# ProPrj__Windows_Hello_DIAL_HUB__2024-08-.net
KiCad netlist of a schematic drawn in EasyEDA Pro
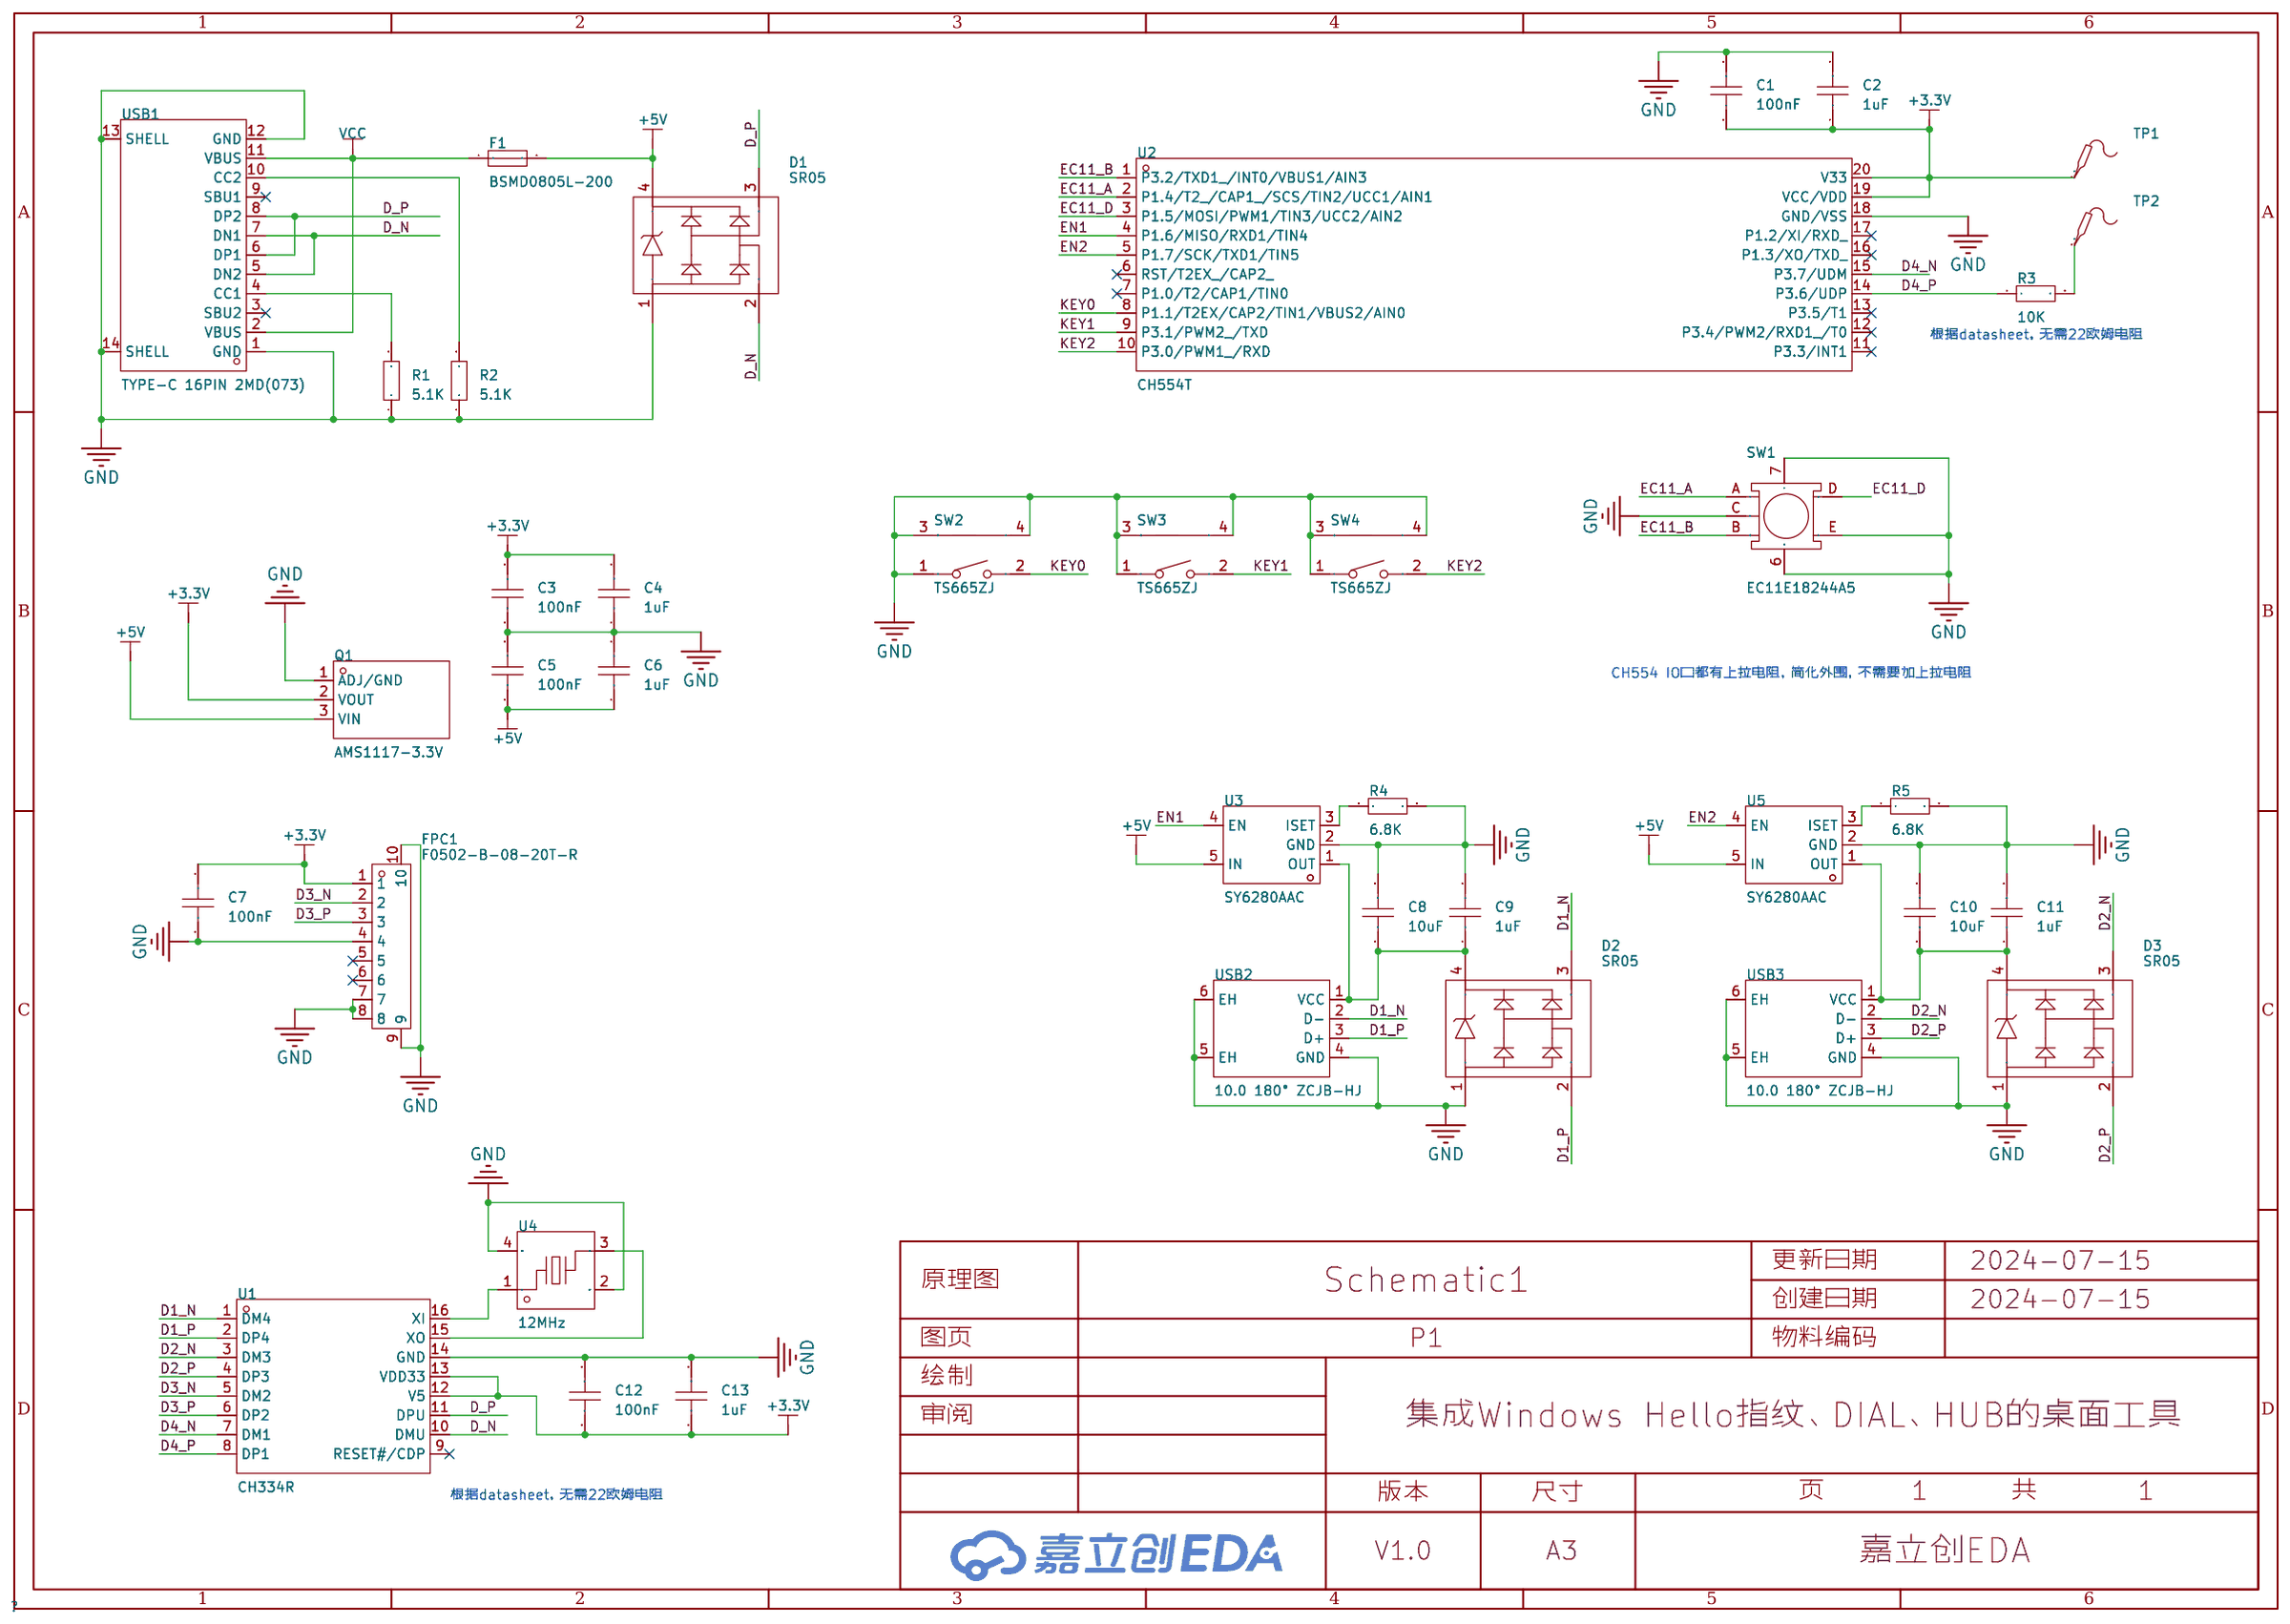
[diagram p0: schematic sheet]

(export (version "E")
  (design (tool "Eeschema 10.0.6"))
  (components
    (comp (ref "C1")
      (value "100nF")
      (footprint "easyedapro:C0603")
      (libsource (lib "easyedapro") (part "CapAcitance"))
    )
    (comp (ref "C2")
      (value "1uF")
      (footprint "easyedapro:C0603")
      (libsource (lib "easyedapro") (part "CapAcitance"))
    )
    (comp (ref "C3")
      (value "100nF")
      (footprint "easyedapro:C0603")
      (libsource (lib "easyedapro") (part "CapAcitance"))
    )
    (comp (ref "C4")
      (value "1uF")
      (footprint "easyedapro:C0603")
      (libsource (lib "easyedapro") (part "CapAcitance"))
    )
    (comp (ref "C5")
      (value "100nF")
      (footprint "easyedapro:C0603")
      (libsource (lib "easyedapro") (part "CapAcitance"))
    )
    (comp (ref "C6")
      (value "1uF")
      (footprint "easyedapro:C0603")
      (libsource (lib "easyedapro") (part "CapAcitance"))
    )
    (comp (ref "C7")
      (value "100nF")
      (footprint "easyedapro:C0603")
      (libsource (lib "easyedapro") (part "CapAcitance"))
    )
    (comp (ref "C8")
      (value "10uF")
      (footprint "easyedapro:C0603")
      (libsource (lib "easyedapro") (part "CapAcitance"))
    )
    (comp (ref "C9")
      (value "1uF")
      (footprint "easyedapro:C0603")
      (libsource (lib "easyedapro") (part "CapAcitance"))
    )
    (comp (ref "C10")
      (value "10uF")
      (footprint "easyedapro:C0603")
      (libsource (lib "easyedapro") (part "CapAcitance"))
    )
    (comp (ref "C11")
      (value "1uF")
      (footprint "easyedapro:C0603")
      (libsource (lib "easyedapro") (part "CapAcitance"))
    )
    (comp (ref "C12")
      (value "100nF")
      (footprint "easyedapro:C0603")
      (libsource (lib "easyedapro") (part "CapAcitance"))
    )
    (comp (ref "C13")
      (value "1uF")
      (footprint "easyedapro:C0603")
      (libsource (lib "easyedapro") (part "CapAcitance"))
    )
    (comp (ref "D1")
      (value "SR05")
      (footprint "easyedapro:SOT-143-4_L2.9-W1.3-P1.90-LS2.4-BL")
      (fields (field (name "Manufacturer") "SEMBO(深波)"))
      (libsource (lib "easyedapro") (part "SR05_C782796"))
    )
    (comp (ref "D2")
      (value "SR05")
      (footprint "easyedapro:SOT-143-4_L2.9-W1.3-P1.90-LS2.4-BL")
      (fields (field (name "Manufacturer") "SEMBO(深波)"))
      (libsource (lib "easyedapro") (part "SR05_C782796"))
    )
    (comp (ref "D3")
      (value "SR05")
      (footprint "easyedapro:SOT-143-4_L2.9-W1.3-P1.90-LS2.4-BL")
      (fields (field (name "Manufacturer") "SEMBO(深波)"))
      (libsource (lib "easyedapro") (part "SR05_C782796"))
    )
    (comp (ref "F1")
      (value "BSMD0805L-200")
      (footprint "easyedapro:F0805")
      (description "最大电压:6V;最大电流:50A;保持电流:2A;跳闸电流:4A;")
      (fields (field (name "Manufacturer") "BHFUSE(佰宏)"))
      (libsource (lib "easyedapro") (part "BSMD0805L-200"))
    )
    (comp (ref "FPC1")
      (value "F0502-B-08-20T-R")
      (footprint "easyedapro:FPC-SMD_F0502-B-08-20T-R")
      (description "锁定特性:翻盖式;触点类型:下接;触点数量:8P;间距:0.5mm;安装类型:卧贴;")
      (fields (field (name "Manufacturer") "XFCN(兴飞)"))
      (libsource (lib "easyedapro") (part "F0502-B-08-20T-R"))
    )
    (comp (ref "Q1")
      (value "AMS1117-3.3V")
      (footprint "easyedapro:SOT-89-3_L4.5-W2.5-P1.50-LS4.2-BR")
      (description "输出类型:固定;最大输入电压:18V;输出电压:3.3V;最大输出电流:1A;输出极性:正极;")
      (fields (field (name "Manufacturer") "MSKSEMI(美森科)"))
      (libsource (lib "easyedapro") (part "AMS1117-3.3V_C5120796"))
    )
    (comp (ref "R1") (value "5.1K") (footprint "easyedapro:R0603") (libsource (lib "easyedapro") (part "电阻")))
    (comp (ref "R2") (value "5.1K") (footprint "easyedapro:R0603") (libsource (lib "easyedapro") (part "电阻")))
    (comp (ref "R3") (value "10K") (footprint "easyedapro:R0603") (libsource (lib "easyedapro") (part "电阻")))
    (comp (ref "R4") (value "6.8K") (footprint "easyedapro:R0603") (libsource (lib "easyedapro") (part "电阻")))
    (comp (ref "R5") (value "6.8K") (footprint "easyedapro:R0603") (libsource (lib "easyedapro") (part "电阻")))
    (comp (ref "SW1")
      (value "EC11E18244A5")
      (footprint "easyedapro:SW-TH_EC11E18244A5")
      (fields (field (name "Manufacturer") "ALPSALPINE(阿尔卑斯阿尔派)"))
      (libsource (lib "easyedapro") (part "EC11E18244A5"))
    )
    (comp (ref "SW2")
      (value "TS665ZJ")
      (footprint "easyedapro:SW-TH_TS665ZJ")
      (fields (field (name "Manufacturer") "SHOU HAN(首韩)"))
      (libsource (lib "easyedapro") (part "TS665ZJ"))
    )
    (comp (ref "SW3")
      (value "TS665ZJ")
      (footprint "easyedapro:SW-TH_TS665ZJ")
      (fields (field (name "Manufacturer") "SHOU HAN(首韩)"))
      (libsource (lib "easyedapro") (part "TS665ZJ"))
    )
    (comp (ref "SW4")
      (value "TS665ZJ")
      (footprint "easyedapro:SW-TH_TS665ZJ")
      (fields (field (name "Manufacturer") "SHOU HAN(首韩)"))
      (libsource (lib "easyedapro") (part "TS665ZJ"))
    )
    (comp (ref "TP1")
      (value "~")
      (footprint "easyedapro:Test-Point-0.5mm")
      (description "Test Point 测试点")
      (libsource (lib "easyedapro") (part "Test-Point"))
    )
    (comp (ref "TP2")
      (value "~")
      (footprint "easyedapro:Test-Point-0.5mm")
      (description "Test Point 测试点")
      (libsource (lib "easyedapro") (part "Test-Point"))
    )
    (comp (ref "U1")
      (value "CH334R")
      (footprint "easyedapro:QSOP-16_L4.9-W3.9-P0.64-LS6.0-BL")
      (fields (field (name "Manufacturer") "WCH(南京沁恒)"))
      (libsource (lib "easyedapro") (part "CH334R"))
    )
    (comp (ref "U2")
      (value "CH554T")
      (footprint "easyedapro:TSSOP-20_L6.5-W4.4-P0.65-LS6.4-TL")
      (fields (field (name "Manufacturer") "WCH(南京沁恒)"))
      (libsource (lib "easyedapro") (part "CH554T_C2928938"))
    )
    (comp (ref "U3")
      (value "SY6280AAC")
      (footprint "easyedapro:SOT-23-5_L3.0-W1.7-P0.95-LS2.8-BL")
      (description "低能耗配电开关")
      (fields (field (name "Manufacturer") "silergy(矽力杰)"))
      (libsource (lib "easyedapro") (part "SY6280AAC"))
    )
    (comp (ref "U4")
      (value "12MHz")
      (footprint "easyedapro:CRYSTAL-SMD_4P-L3.2-W2.5-BL")
      (description "频率:12MHz;常温频差:±10ppm;外接负载电容:12pF;频率稳定度(全温):±30ppm;")
      (fields
        (field (name "Manufacturer Part") "X322541201210A")
        (field (name "Manufacturer") "Starwave(思大)")
      )
      (libsource (lib "easyedapro") (part "X322541201210A"))
    )
    (comp (ref "U5")
      (value "SY6280AAC")
      (footprint "easyedapro:SOT-23-5_L3.0-W1.7-P0.95-LS2.8-BL")
      (description "低能耗配电开关")
      (fields (field (name "Manufacturer") "silergy(矽力杰)"))
      (libsource (lib "easyedapro") (part "SY6280AAC"))
    )
    (comp (ref "USB1")
      (value "TYPE-C 16PIN 2MD(073)")
      (footprint "easyedapro:USB-C-SMD_TYPE-C-6PIN-2MD-073")
      (description "连接器类型:Type-C;标准:-;公母:母;端口数量:1;触点数量:16P;安装方式:卧贴;额定电流 - 电源:5A;工作温度范围:-25°C~+85°C;")
      (fields (field (name "Manufacturer") "SHOU HAN(首韩)"))
      (libsource (lib "easyedapro") (part "TYPE-C 16PIN 2MD(073)"))
    )
    (comp (ref "USB2")
      (value "10.0 180° ZCJB-HJ")
      (footprint "easyedapro:USB-A-TH_ZCJB-HJ")
      (description "连接器类型:Type-A;标准:USB 2.0;公母:母;端口数量:1;触点数量:4P;安装方式:直插;额定电流 - 电源:1.5A;工作温度范围:-25°C~+85°C;")
      (fields (field (name "Manufacturer") "SHOU HAN(首韩)"))
      (libsource (lib "easyedapro") (part "10.0 180° ZCJB-HJ"))
    )
    (comp (ref "USB3")
      (value "10.0 180° ZCJB-HJ")
      (footprint "easyedapro:USB-A-TH_ZCJB-HJ")
      (description "连接器类型:Type-A;标准:USB 2.0;公母:母;端口数量:1;触点数量:4P;安装方式:直插;额定电流 - 电源:1.5A;工作温度范围:-25°C~+85°C;")
      (fields (field (name "Manufacturer") "SHOU HAN(首韩)"))
      (libsource (lib "easyedapro") (part "10.0 180° ZCJB-HJ"))
    )
  )
  (nets
    (net (code "1") (name "+3.3V") (class "Default")
      (node (ref "C1") (pin "1") (pinfunction "1_1") (pintype "input"))
      (node (ref "C12") (pin "1") (pinfunction "1_1") (pintype "input"))
      (node (ref "C13") (pin "1") (pinfunction "1_1") (pintype "input"))
      (node (ref "C2") (pin "1") (pinfunction "1_1") (pintype "input"))
      (node (ref "C3") (pin "2") (pinfunction "2_2") (pintype "input"))
      (node (ref "C4") (pin "2") (pinfunction "2_2") (pintype "input"))
      (node (ref "C7") (pin "1") (pinfunction "1_1") (pintype "input"))
      (node (ref "FPC1") (pin "1") (pinfunction "1_1") (pintype "unspecified"))
      (node (ref "Q1") (pin "2") (pinfunction "VOUT_2") (pintype "unspecified"))
      (node (ref "TP1") (pin "1") (pinfunction "1_1") (pintype "input"))
      (node (ref "U1") (pin "12") (pinfunction "V5_12") (pintype "unspecified"))
      (node (ref "U1") (pin "13") (pinfunction "VDD33_13") (pintype "unspecified"))
      (node (ref "U2") (pin "19") (pinfunction "VCC/VDD_19") (pintype "unspecified"))
      (node (ref "U2") (pin "20") (pinfunction "V33_20") (pintype "unspecified"))
    )
    (net (code "2") (name "+5V") (class "Default")
      (node (ref "C5") (pin "1") (pinfunction "1_1") (pintype "input"))
      (node (ref "C6") (pin "1") (pinfunction "1_1") (pintype "input"))
      (node (ref "D1") (pin "4") (pinfunction "4_4") (pintype "unspecified"))
      (node (ref "F1") (pin "2") (pinfunction "2_2") (pintype "unspecified"))
      (node (ref "Q1") (pin "3") (pinfunction "VIN_3") (pintype "unspecified"))
      (node (ref "U3") (pin "5") (pinfunction "IN_5") (pintype "unspecified"))
      (node (ref "U5") (pin "5") (pinfunction "IN_5") (pintype "unspecified"))
    )
    (net (code "3") (name "/D1_N") (class "Default")
      (node (ref "D2") (pin "3") (pinfunction "3_3") (pintype "unspecified"))
      (node (ref "U1") (pin "1") (pinfunction "DM4_1") (pintype "unspecified"))
      (node (ref "USB2") (pin "2") (pinfunction "D-_2") (pintype "input"))
    )
    (net (code "4") (name "/D1_P") (class "Default")
      (node (ref "D2") (pin "2") (pinfunction "2_2") (pintype "unspecified"))
      (node (ref "U1") (pin "2") (pinfunction "DP4_2") (pintype "unspecified"))
      (node (ref "USB2") (pin "3") (pinfunction "D+_3") (pintype "input"))
    )
    (net (code "5") (name "/D2_N") (class "Default")
      (node (ref "D3") (pin "3") (pinfunction "3_3") (pintype "unspecified"))
      (node (ref "U1") (pin "3") (pinfunction "DM3_3") (pintype "unspecified"))
      (node (ref "USB3") (pin "2") (pinfunction "D-_2") (pintype "input"))
    )
    (net (code "6") (name "/D2_P") (class "Default")
      (node (ref "D3") (pin "2") (pinfunction "2_2") (pintype "unspecified"))
      (node (ref "U1") (pin "4") (pinfunction "DP3_4") (pintype "unspecified"))
      (node (ref "USB3") (pin "3") (pinfunction "D+_3") (pintype "input"))
    )
    (net (code "7") (name "/D3_N") (class "Default")
      (node (ref "FPC1") (pin "2") (pinfunction "2_2") (pintype "unspecified"))
      (node (ref "U1") (pin "5") (pinfunction "DM2_5") (pintype "unspecified"))
    )
    (net (code "8") (name "/D3_P") (class "Default")
      (node (ref "FPC1") (pin "3") (pinfunction "3_3") (pintype "unspecified"))
      (node (ref "U1") (pin "6") (pinfunction "DP2_6") (pintype "unspecified"))
    )
    (net (code "9") (name "/D4_N") (class "Default")
      (node (ref "U1") (pin "7") (pinfunction "DM1_7") (pintype "unspecified"))
      (node (ref "U2") (pin "15") (pinfunction "P3.7/UDM_15") (pintype "unspecified"))
    )
    (net (code "10") (name "/D4_P") (class "Default")
      (node (ref "R3") (pin "1") (pinfunction "1_1") (pintype "input"))
      (node (ref "U1") (pin "8") (pinfunction "DP1_8") (pintype "unspecified"))
      (node (ref "U2") (pin "14") (pinfunction "P3.6/UDP_14") (pintype "unspecified"))
    )
    (net (code "11") (name "/D_N") (class "Default")
      (node (ref "D1") (pin "2") (pinfunction "2_2") (pintype "unspecified"))
      (node (ref "U1") (pin "10") (pinfunction "DMU_10") (pintype "unspecified"))
      (node (ref "USB1") (pin "5") (pinfunction "DN2_5") (pintype "unspecified"))
      (node (ref "USB1") (pin "7") (pinfunction "DN1_7") (pintype "unspecified"))
    )
    (net (code "12") (name "/D_P") (class "Default")
      (node (ref "D1") (pin "3") (pinfunction "3_3") (pintype "unspecified"))
      (node (ref "U1") (pin "11") (pinfunction "DPU_11") (pintype "unspecified"))
      (node (ref "USB1") (pin "6") (pinfunction "DP1_6") (pintype "unspecified"))
      (node (ref "USB1") (pin "8") (pinfunction "DP2_8") (pintype "unspecified"))
    )
    (net (code "13") (name "/EC11_A") (class "Default")
      (node (ref "SW1") (pin "A") (pinfunction "A_A") (pintype "unspecified"))
      (node (ref "U2") (pin "2") (pinfunction "P1.4/T2_/CAP1_/SCS/TIN2/UCC1/AIN1_2") (pintype "unspecified"))
    )
    (net (code "14") (name "/EC11_B") (class "Default")
      (node (ref "SW1") (pin "B") (pinfunction "B_B") (pintype "unspecified"))
      (node (ref "U2") (pin "1") (pinfunction "P3.2/TXD1_/INT0/VBUS1/AIN3_1") (pintype "unspecified"))
    )
    (net (code "15") (name "/EC11_D") (class "Default")
      (node (ref "SW1") (pin "D") (pinfunction "D_D") (pintype "unspecified"))
      (node (ref "U2") (pin "3") (pinfunction "P1.5/MOSI/PWM1/TIN3/UCC2/AIN2_3") (pintype "unspecified"))
    )
    (net (code "16") (name "/EN1") (class "Default")
      (node (ref "U2") (pin "4") (pinfunction "P1.6/MISO/RXD1/TIN4_4") (pintype "unspecified"))
      (node (ref "U3") (pin "4") (pinfunction "EN_4") (pintype "unspecified"))
    )
    (net (code "17") (name "/EN2") (class "Default")
      (node (ref "U2") (pin "5") (pinfunction "P1.7/SCK/TXD1/TIN5_5") (pintype "unspecified"))
      (node (ref "U5") (pin "4") (pinfunction "EN_4") (pintype "unspecified"))
    )
    (net (code "18") (name "/KEY0") (class "Default")
      (node (ref "SW2") (pin "2") (pinfunction "2_2") (pintype "input"))
      (node (ref "U2") (pin "8") (pinfunction "P1.1/T2EX/CAP2/TIN1/VBUS2/AIN0_8") (pintype "unspecified"))
    )
    (net (code "19") (name "/KEY1") (class "Default")
      (node (ref "SW3") (pin "2") (pinfunction "2_2") (pintype "input"))
      (node (ref "U2") (pin "9") (pinfunction "P3.1/PWM2_/TXD_9") (pintype "unspecified"))
    )
    (net (code "20") (name "/KEY2") (class "Default")
      (node (ref "SW4") (pin "2") (pinfunction "2_2") (pintype "input"))
      (node (ref "U2") (pin "10") (pinfunction "P3.0/PWM1_/RXD_10") (pintype "unspecified"))
    )
    (net (code "21") (name "GND") (class "Default")
      (node (ref "C1") (pin "2") (pinfunction "2_2") (pintype "input"))
      (node (ref "C10") (pin "2") (pinfunction "2_2") (pintype "input"))
      (node (ref "C11") (pin "2") (pinfunction "2_2") (pintype "input"))
      (node (ref "C12") (pin "2") (pinfunction "2_2") (pintype "input"))
      (node (ref "C13") (pin "2") (pinfunction "2_2") (pintype "input"))
      (node (ref "C2") (pin "2") (pinfunction "2_2") (pintype "input"))
      (node (ref "C3") (pin "1") (pinfunction "1_1") (pintype "input"))
      (node (ref "C4") (pin "1") (pinfunction "1_1") (pintype "input"))
      (node (ref "C5") (pin "2") (pinfunction "2_2") (pintype "input"))
      (node (ref "C6") (pin "2") (pinfunction "2_2") (pintype "input"))
      (node (ref "C7") (pin "2") (pinfunction "2_2") (pintype "input"))
      (node (ref "C8") (pin "2") (pinfunction "2_2") (pintype "input"))
      (node (ref "C9") (pin "2") (pinfunction "2_2") (pintype "input"))
      (node (ref "D1") (pin "1") (pinfunction "1_1") (pintype "unspecified"))
      (node (ref "D2") (pin "1") (pinfunction "1_1") (pintype "unspecified"))
      (node (ref "D3") (pin "1") (pinfunction "1_1") (pintype "unspecified"))
      (node (ref "FPC1") (pin "10") (pinfunction "10_10") (pintype "unspecified"))
      (node (ref "FPC1") (pin "4") (pinfunction "4_4") (pintype "unspecified"))
      (node (ref "FPC1") (pin "7") (pinfunction "7_7") (pintype "unspecified"))
      (node (ref "FPC1") (pin "8") (pinfunction "8_8") (pintype "unspecified"))
      (node (ref "FPC1") (pin "9") (pinfunction "9_9") (pintype "unspecified"))
      (node (ref "Q1") (pin "1") (pinfunction "ADJ/GND_1") (pintype "unspecified"))
      (node (ref "R1") (pin "1") (pinfunction "1_1") (pintype "input"))
      (node (ref "R2") (pin "1") (pinfunction "1_1") (pintype "input"))
      (node (ref "R4") (pin "2") (pinfunction "2_2") (pintype "input"))
      (node (ref "R5") (pin "2") (pinfunction "2_2") (pintype "input"))
      (node (ref "SW1") (pin "6") (pinfunction "6_6") (pintype "unspecified"))
      (node (ref "SW1") (pin "7") (pinfunction "7_7") (pintype "unspecified"))
      (node (ref "SW1") (pin "C") (pinfunction "C_C") (pintype "unspecified"))
      (node (ref "SW1") (pin "E") (pinfunction "E_E") (pintype "unspecified"))
      (node (ref "SW2") (pin "1") (pinfunction "1_1") (pintype "input"))
      (node (ref "SW2") (pin "3") (pinfunction "3_3") (pintype "input"))
      (node (ref "SW2") (pin "4") (pinfunction "4_4") (pintype "input"))
      (node (ref "SW3") (pin "1") (pinfunction "1_1") (pintype "input"))
      (node (ref "SW3") (pin "3") (pinfunction "3_3") (pintype "input"))
      (node (ref "SW3") (pin "4") (pinfunction "4_4") (pintype "input"))
      (node (ref "SW4") (pin "1") (pinfunction "1_1") (pintype "input"))
      (node (ref "SW4") (pin "3") (pinfunction "3_3") (pintype "input"))
      (node (ref "SW4") (pin "4") (pinfunction "4_4") (pintype "input"))
      (node (ref "U1") (pin "14") (pinfunction "GND_14") (pintype "unspecified"))
      (node (ref "U2") (pin "18") (pinfunction "GND/VSS_18") (pintype "unspecified"))
      (node (ref "U3") (pin "2") (pinfunction "GND_2") (pintype "unspecified"))
      (node (ref "U4") (pin "2") (pinfunction "GND_2") (pintype "input"))
      (node (ref "U4") (pin "4") (pinfunction "GND_4") (pintype "input"))
      (node (ref "U5") (pin "2") (pinfunction "GND_2") (pintype "unspecified"))
      (node (ref "USB1") (pin "1") (pinfunction "GND_1") (pintype "unspecified"))
      (node (ref "USB1") (pin "12") (pinfunction "GND_12") (pintype "unspecified"))
      (node (ref "USB1") (pin "13") (pinfunction "SHELL_13") (pintype "unspecified"))
      (node (ref "USB1") (pin "14") (pinfunction "SHELL_14") (pintype "unspecified"))
      (node (ref "USB2") (pin "4") (pinfunction "GND_4") (pintype "input"))
      (node (ref "USB2") (pin "5") (pinfunction "EH_5") (pintype "unspecified"))
      (node (ref "USB2") (pin "6") (pinfunction "EH_6") (pintype "unspecified"))
      (node (ref "USB3") (pin "4") (pinfunction "GND_4") (pintype "input"))
      (node (ref "USB3") (pin "5") (pinfunction "EH_5") (pintype "unspecified"))
      (node (ref "USB3") (pin "6") (pinfunction "EH_6") (pintype "unspecified"))
    )
    (net (code "22") (name "Net-(R3-Pad2)") (class "Default")
      (node (ref "R3") (pin "2") (pinfunction "2_2") (pintype "input"))
      (node (ref "TP2") (pin "1") (pinfunction "1_1") (pintype "input"))
    )
    (net (code "23") (name "Net-(U1-XI)") (class "Default")
      (node (ref "U1") (pin "16") (pinfunction "XI_16") (pintype "unspecified"))
      (node (ref "U4") (pin "1") (pinfunction "1_1") (pintype "input"))
    )
    (net (code "24") (name "Net-(U1-XO)") (class "Default")
      (node (ref "U1") (pin "15") (pinfunction "XO_15") (pintype "unspecified"))
      (node (ref "U4") (pin "3") (pinfunction "3_3") (pintype "input"))
    )
    (net (code "25") (name "Net-(U3-ISET)") (class "Default")
      (node (ref "R4") (pin "1") (pinfunction "1_1") (pintype "input"))
      (node (ref "U3") (pin "3") (pinfunction "ISET_3") (pintype "unspecified"))
    )
    (net (code "26") (name "Net-(U3-OUT)") (class "Default")
      (node (ref "C8") (pin "1") (pinfunction "1_1") (pintype "input"))
      (node (ref "C9") (pin "1") (pinfunction "1_1") (pintype "input"))
      (node (ref "D2") (pin "4") (pinfunction "4_4") (pintype "unspecified"))
      (node (ref "U3") (pin "1") (pinfunction "OUT_1") (pintype "unspecified"))
      (node (ref "USB2") (pin "1") (pinfunction "VCC_1") (pintype "input"))
    )
    (net (code "27") (name "Net-(U5-ISET)") (class "Default")
      (node (ref "R5") (pin "1") (pinfunction "1_1") (pintype "input"))
      (node (ref "U5") (pin "3") (pinfunction "ISET_3") (pintype "unspecified"))
    )
    (net (code "28") (name "Net-(U5-OUT)") (class "Default")
      (node (ref "C10") (pin "1") (pinfunction "1_1") (pintype "input"))
      (node (ref "C11") (pin "1") (pinfunction "1_1") (pintype "input"))
      (node (ref "D3") (pin "4") (pinfunction "4_4") (pintype "unspecified"))
      (node (ref "U5") (pin "1") (pinfunction "OUT_1") (pintype "unspecified"))
      (node (ref "USB3") (pin "1") (pinfunction "VCC_1") (pintype "input"))
    )
    (net (code "29") (name "Net-(USB1-CC1)") (class "Default")
      (node (ref "R1") (pin "2") (pinfunction "2_2") (pintype "input"))
      (node (ref "USB1") (pin "4") (pinfunction "CC1_4") (pintype "unspecified"))
    )
    (net (code "30") (name "Net-(USB1-CC2)") (class "Default")
      (node (ref "R2") (pin "2") (pinfunction "2_2") (pintype "input"))
      (node (ref "USB1") (pin "10") (pinfunction "CC2_10") (pintype "unspecified"))
    )
    (net (code "31") (name "VCC") (class "Default")
      (node (ref "F1") (pin "1") (pinfunction "1_1") (pintype "unspecified"))
      (node (ref "USB1") (pin "11") (pinfunction "VBUS_11") (pintype "unspecified"))
      (node (ref "USB1") (pin "2") (pinfunction "VBUS_2") (pintype "unspecified"))
    )
    (net (code "32") (name "unconnected-(FPC1-Pad5)") (class "Default")
      (node (ref "FPC1") (pin "5") (pinfunction "5_5") (pintype "unspecified+no_connect"))
    )
    (net (code "33") (name "unconnected-(FPC1-Pad6)") (class "Default")
      (node (ref "FPC1") (pin "6") (pinfunction "6_6") (pintype "unspecified+no_connect"))
    )
    (net (code "34") (name "unconnected-(U1-RESET#{slash}CDP-Pad9)") (class "Default")
      (node (ref "U1") (pin "9") (pinfunction "RESET#/CDP_9") (pintype "unspecified+no_connect"))
    )
    (net (code "35") (name "unconnected-(U2-P1.0{slash}T2{slash}CAP1{slash}TIN0-Pad7)") (class "Default")
      (node (ref "U2") (pin "7") (pinfunction "P1.0/T2/CAP1/TIN0_7") (pintype "unspecified+no_connect"))
    )
    (net (code "36") (name "unconnected-(U2-P1.2{slash}XI{slash}RXD_-Pad17)") (class "Default")
      (node (ref "U2") (pin "17") (pinfunction "P1.2/XI/RXD__17") (pintype "unspecified+no_connect"))
    )
    (net (code "37") (name "unconnected-(U2-P1.3{slash}XO{slash}TXD_-Pad16)") (class "Default")
      (node (ref "U2") (pin "16") (pinfunction "P1.3/XO/TXD__16") (pintype "unspecified+no_connect"))
    )
    (net (code "38") (name "unconnected-(U2-P3.3{slash}INT1-Pad11)") (class "Default")
      (node (ref "U2") (pin "11") (pinfunction "P3.3/INT1_11") (pintype "unspecified+no_connect"))
    )
    (net (code "39") (name "unconnected-(U2-P3.4{slash}PWM2{slash}RXD1_{slash}T0-Pad12)") (class "Default")
      (node (ref "U2") (pin "12") (pinfunction "P3.4/PWM2/RXD1_/T0_12") (pintype "unspecified+no_connect"))
    )
    (net (code "40") (name "unconnected-(U2-P3.5{slash}T1-Pad13)") (class "Default")
      (node (ref "U2") (pin "13") (pinfunction "P3.5/T1_13") (pintype "unspecified+no_connect"))
    )
    (net (code "41") (name "unconnected-(U2-RST{slash}T2EX_{slash}CAP2_-Pad6)") (class "Default")
      (node (ref "U2") (pin "6") (pinfunction "RST/T2EX_/CAP2__6") (pintype "unspecified+no_connect"))
    )
    (net (code "42") (name "unconnected-(USB1-SBU1-Pad9)") (class "Default")
      (node (ref "USB1") (pin "9") (pinfunction "SBU1_9") (pintype "unspecified+no_connect"))
    )
    (net (code "43") (name "unconnected-(USB1-SBU2-Pad3)") (class "Default")
      (node (ref "USB1") (pin "3") (pinfunction "SBU2_3") (pintype "unspecified+no_connect"))
    )
  )
)
